# Sheet1.net
KiCad netlist of a schematic drawn in Altium Designer
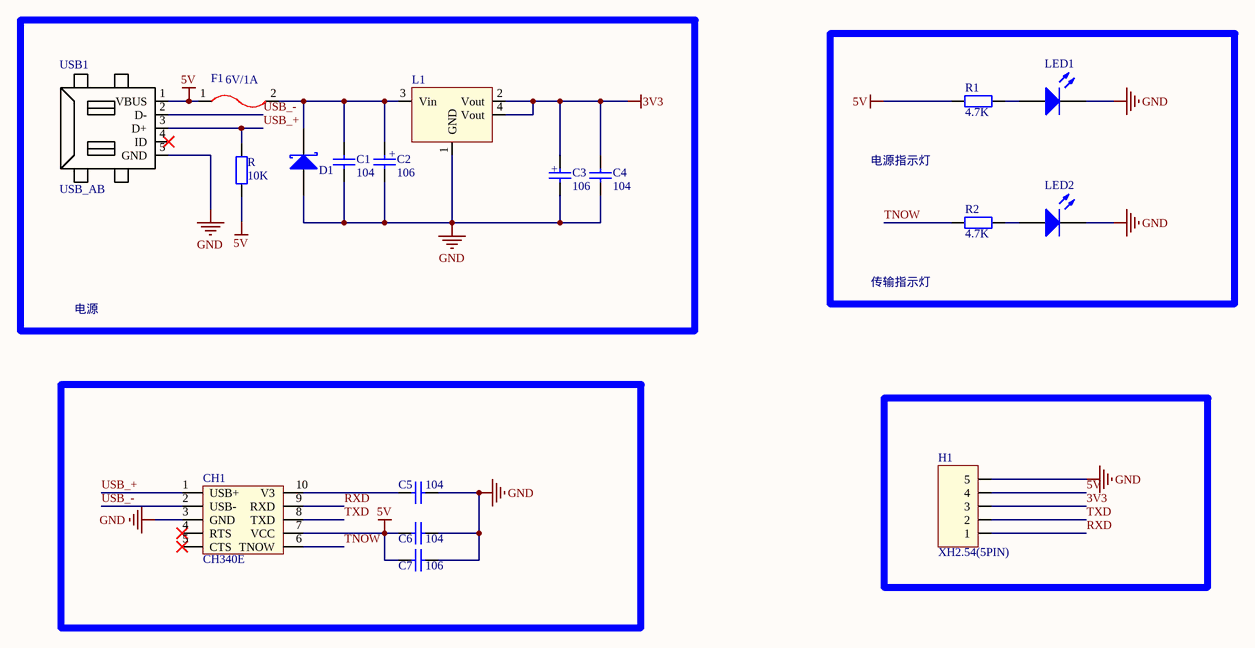
[diagram p0: Sheet1.SchDoc]

(export (version "E")
  (design (tool "Eeschema 10.0.6"))
  (components
    (comp (ref "C1") (value "104") (footprint "C_SOP_0603") (libsource (lib "DG") (part "C_SMD")))
    (comp (ref "C2") (value "106") (footprint "C_SOP_1206") (libsource (lib "DG") (part "C_SMD")))
    (comp (ref "C3") (value "106") (footprint "C_SOP_1206") (libsource (lib "DG") (part "C_SMD")))
    (comp (ref "C4") (value "104") (footprint "C_SOP_0603") (libsource (lib "DG") (part "C_SMD")))
    (comp (ref "C5") (value "104") (footprint "C_SOP_0603") (libsource (lib "DG") (part "C_SMD")))
    (comp (ref "C6") (value "104") (footprint "C_SOP_0603") (libsource (lib "DG") (part "C_SMD")))
    (comp (ref "C7") (value "106") (footprint "C_SOP_0603") (libsource (lib "DG") (part "C_SMD")))
    (comp (ref "CH1") (value "CH340E") (footprint "MSOP_10") (libsource (lib "DG") (part "CH340E")))
    (comp (ref "D1") (value "DIODE") (footprint "LC-SMA(DO-214AC)_S5") (libsource (lib "DG") (part "DIODE")))
    (comp (ref "F1") (value "6V/1A") (footprint "Fuse_0805") (libsource (lib "DG") (part "FUSE")))
    (comp (ref "H1")
      (value "XH2.54(5PIN)")
      (footprint "Header 2.54X5")
      (libsource (lib "DG") (part "XH2.54(5PIN)"))
    )
    (comp (ref "L1")
      (value "LDO-3.3-AMS1117")
      (footprint "SOT223_3")
      (libsource (lib "DG") (part "LDO-3.3-AMS1117"))
    )
    (comp (ref "LED1") (value "LED") (footprint "LED_0603_R") (libsource (lib "DG") (part "LED")))
    (comp (ref "LED2") (value "LED") (footprint "LED_0603_R") (libsource (lib "DG") (part "LED")))
    (comp (ref "R") (value "10K") (footprint "R_SMD_0603") (libsource (lib "DG") (part "R_SMD")))
    (comp (ref "R1") (value "4.7K") (footprint "R_SMD_0603") (libsource (lib "") (part "R_SMD_1")))
    (comp (ref "R2") (value "4.7K") (footprint "R_SMD_0603") (libsource (lib "") (part "R_SMD_1")))
    (comp (ref "USB1") (value "USB_AB") (footprint "USB_MINI_SMD") (libsource (lib "DG") (part "USB_AB")))
  )
  (nets
    (net (code "1") (name "/RXD") (class "Default")
      (node (ref "CH1") (pin "9") (pinfunction "RXD_9") (pintype "passive"))
      (node (ref "H1") (pin "1") (pinfunction "1_1") (pintype "passive"))
    )
    (net (code "2") (name "/TNOW") (class "Default")
      (node (ref "CH1") (pin "6") (pinfunction "TNOW_6") (pintype "passive"))
      (node (ref "R2") (pin "1") (pinfunction "1_1") (pintype "passive"))
    )
    (net (code "3") (name "/TXD") (class "Default")
      (node (ref "CH1") (pin "8") (pinfunction "TXD_8") (pintype "passive"))
      (node (ref "H1") (pin "2") (pinfunction "2_2") (pintype "passive"))
    )
    (net (code "4") (name "/USB_+") (class "Default")
      (node (ref "CH1") (pin "1") (pinfunction "USB+_1") (pintype "passive"))
      (node (ref "R") (pin "2") (pinfunction "2_2") (pintype "passive"))
      (node (ref "USB1") (pin "3") (pinfunction "D+_3") (pintype "passive"))
    )
    (net (code "5") (name "/USB_-") (class "Default")
      (node (ref "CH1") (pin "2") (pinfunction "USB-_2") (pintype "passive"))
      (node (ref "USB1") (pin "2") (pinfunction "D-_2") (pintype "passive"))
    )
    (net (code "6") (name "3V3") (class "Default")
      (node (ref "C3") (pin "1") (pinfunction "1_1") (pintype "passive"))
      (node (ref "C4") (pin "1") (pinfunction "1_1") (pintype "passive"))
      (node (ref "H1") (pin "3") (pinfunction "3_3") (pintype "passive"))
      (node (ref "L1") (pin "2") (pinfunction "Vout_2") (pintype "passive"))
      (node (ref "L1") (pin "4") (pinfunction "Vout_4") (pintype "passive"))
    )
    (net (code "7") (name "5V") (class "Default")
      (node (ref "C6") (pin "1") (pinfunction "1_1") (pintype "passive"))
      (node (ref "C7") (pin "1") (pinfunction "1_1") (pintype "passive"))
      (node (ref "CH1") (pin "7") (pinfunction "VCC_7") (pintype "passive"))
      (node (ref "F1") (pin "1") (pinfunction "OUT_1") (pintype "passive"))
      (node (ref "H1") (pin "4") (pinfunction "4_4") (pintype "passive"))
      (node (ref "R") (pin "1") (pinfunction "1_1") (pintype "passive"))
      (node (ref "R1") (pin "1") (pinfunction "1_1") (pintype "passive"))
      (node (ref "USB1") (pin "1") (pinfunction "VBUS_1") (pintype "passive"))
    )
    (net (code "8") (name "GND") (class "Default")
      (node (ref "C1") (pin "1") (pinfunction "1_1") (pintype "passive"))
      (node (ref "C2") (pin "1") (pinfunction "1_1") (pintype "passive"))
      (node (ref "C3") (pin "2") (pinfunction "2_2") (pintype "passive"))
      (node (ref "C4") (pin "2") (pinfunction "2_2") (pintype "passive"))
      (node (ref "C5") (pin "2") (pinfunction "2_2") (pintype "passive"))
      (node (ref "C6") (pin "2") (pinfunction "2_2") (pintype "passive"))
      (node (ref "C7") (pin "2") (pinfunction "2_2") (pintype "passive"))
      (node (ref "CH1") (pin "3") (pinfunction "GND_3") (pintype "passive"))
      (node (ref "D1") (pin "2") (pinfunction "A_2") (pintype "passive"))
      (node (ref "H1") (pin "5") (pinfunction "5_5") (pintype "passive"))
      (node (ref "L1") (pin "1") (pinfunction "GND_1") (pintype "passive"))
      (node (ref "LED1") (pin "2") (pinfunction "K_2") (pintype "passive"))
      (node (ref "LED2") (pin "2") (pinfunction "K_2") (pintype "passive"))
      (node (ref "USB1") (pin "5") (pinfunction "GND_5") (pintype "passive"))
    )
    (net (code "9") (name "Net-(CH1-V3)") (class "Default")
      (node (ref "C5") (pin "1") (pinfunction "1_1") (pintype "passive"))
      (node (ref "CH1") (pin "10") (pinfunction "V3_10") (pintype "passive"))
    )
    (net (code "10") (name "Net-(D1-K)") (class "Default")
      (node (ref "C1") (pin "2") (pinfunction "2_2") (pintype "passive"))
      (node (ref "C2") (pin "2") (pinfunction "2_2") (pintype "passive"))
      (node (ref "D1") (pin "1") (pinfunction "K_1") (pintype "passive"))
      (node (ref "F1") (pin "2") (pinfunction "OUT_2") (pintype "passive"))
      (node (ref "L1") (pin "3") (pinfunction "Vin_3") (pintype "passive"))
    )
    (net (code "11") (name "Net-(LED1-A)") (class "Default")
      (node (ref "LED1") (pin "1") (pinfunction "A_1") (pintype "passive"))
      (node (ref "R1") (pin "2") (pinfunction "2_2") (pintype "passive"))
    )
    (net (code "12") (name "Net-(LED2-A)") (class "Default")
      (node (ref "LED2") (pin "1") (pinfunction "A_1") (pintype "passive"))
      (node (ref "R2") (pin "2") (pinfunction "2_2") (pintype "passive"))
    )
    (net (code "13") (name "unconnected-(CH1-CTS-Pad5)") (class "Default")
      (node (ref "CH1") (pin "5") (pinfunction "CTS_5") (pintype "passive+no_connect"))
    )
    (net (code "14") (name "unconnected-(CH1-RTS-Pad4)") (class "Default")
      (node (ref "CH1") (pin "4") (pinfunction "RTS_4") (pintype "passive+no_connect"))
    )
    (net (code "15") (name "unconnected-(USB1-ID-Pad4)") (class "Default")
      (node (ref "USB1") (pin "4") (pinfunction "ID_4") (pintype "passive+no_connect"))
    )
  )
)
